# RLC_LPF.net
KiCad netlist of a schematic drawn in Altium Designer
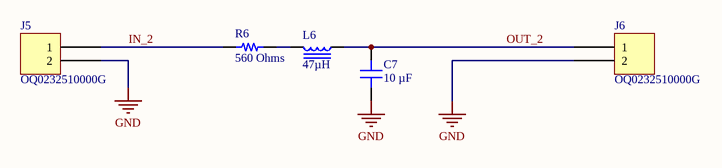
[diagram p0: RLC_LPF.SchDoc]

(export (version "E")
  (design (tool "Eeschema 10.0.6"))
  (components
    (comp (ref "C7")
      (value "10 µF")
      (footprint "CAP 0603_1608")
      (description "CAP CER 10UF 10V X5R 0603")
      (fields
        (field (name "PART NUMBER") "MD0603BW106M100NHT-EM")
        (field (name "MANUFACTURER") "Knowles Novacap")
      )
      (libsource (lib "Celestial Altium Library - altium_library") (part "Capacitor"))
    )
    (comp (ref "J5")
      (value "OQ0232510000G")
      (footprint "FCI 06-381-2PIN")
      (description "TERM BLOCK HDR 2POS 90DEG 3.81MM")
      (fields (field (name "MANUFACTURER") "Amphenol Anytek"))
      (libsource (lib "") (part "2 Pin_1"))
    )
    (comp (ref "J6")
      (value "OQ0232510000G")
      (footprint "FCI 06-381-2PIN")
      (description "TERM BLOCK HDR 2POS 90DEG 3.81MM")
      (fields (field (name "MANUFACTURER") "Amphenol Anytek"))
      (libsource (lib "Celestial Altium Library - altium_library") (part "2 Pin"))
    )
    (comp (ref "L6")
      (value "47µH")
      (footprint "IND 0603_1608 RF WW")
      (description "INDUCTORPOWER LINE 0603 47H 20%")
      (fields (field (name "PART NUMBER") "L0603B470MPWFT") (field (name "MANUFACTURER") "KEMET"))
      (libsource (lib "Celestial Altium Library - altium_library") (part "Inductor"))
    )
    (comp (ref "R6")
      (value "560 Ohms")
      (footprint "RES 0603_1608")
      (description "RES 560 OHM 1% 1/4W 0603")
      (fields
        (field (name "PART NUMBER") "CRGP0603F560R")
        (field (name "MANUFACTURER") "TE Connectivity Passive Product")
      )
      (libsource (lib "Celestial Altium Library - altium_library") (part "Resistor"))
    )
  )
  (nets
    (net (code "1") (name "/IN_2") (class "Default")
      (node (ref "J5") (pin "1") (pinfunction "1_1") (pintype "passive"))
      (node (ref "R6") (pin "1") (pinfunction "1_1") (pintype "passive"))
    )
    (net (code "2") (name "/OUT_2") (class "Default")
      (node (ref "C7") (pin "2") (pinfunction "2_2") (pintype "passive"))
      (node (ref "J6") (pin "1") (pinfunction "1_1") (pintype "passive"))
      (node (ref "L6") (pin "1") (pinfunction "1_1") (pintype "passive"))
    )
    (net (code "3") (name "GND") (class "Default")
      (node (ref "C7") (pin "1") (pinfunction "1_1") (pintype "passive"))
      (node (ref "J5") (pin "2") (pinfunction "2_2") (pintype "passive"))
      (node (ref "J6") (pin "2") (pinfunction "2_2") (pintype "passive"))
    )
    (net (code "4") (name "Net-(L6-Pad2)") (class "Default")
      (node (ref "L6") (pin "2") (pinfunction "2_2") (pintype "passive"))
      (node (ref "R6") (pin "2") (pinfunction "2_2") (pintype "passive"))
    )
  )
)
